# AnalogKeyPad.net
KiCad netlist of a schematic drawn in EAGLE
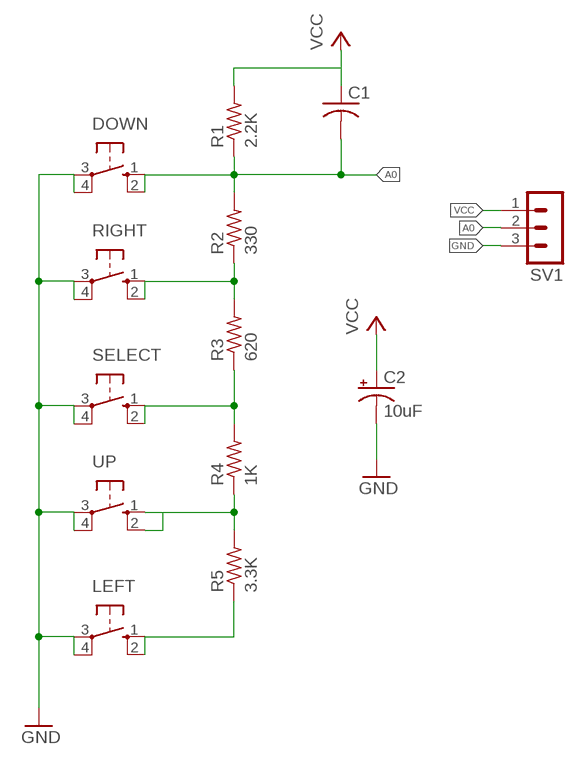
[diagram p0: schematic, sheet 1]

(export (version "E")
  (design (tool "Eeschema 10.0.6"))
  (components
    (comp (ref "C1")
      (value "C-US050-024X044")
      (footprint "eagle-import:C050-024X044")
      (libsource (lib "eagle-import") (part "C-US050-024X044"))
    )
    (comp (ref "C2")
      (value "10uF")
      (footprint "eagle-import:E2,5-6E")
      (libsource (lib "eagle-import") (part "CPOL-USE2,5-6E"))
    )
    (comp (ref "DOWN")
      (value "10-XX")
      (footprint "eagle-import:B3F-10XX")
      (fields (field (name "MPN") "B3F-1000"))
      (libsource (lib "eagle-import") (part "10-XX"))
    )
    (comp (ref "LEFT")
      (value "10-XX")
      (footprint "eagle-import:B3F-10XX")
      (fields (field (name "MPN") "B3F-1000"))
      (libsource (lib "eagle-import") (part "10-XX"))
    )
    (comp (ref "R1")
      (value "2.2K")
      (footprint "eagle-import:0207_7")
      (libsource (lib "eagle-import") (part "R-US_0207/7"))
    )
    (comp (ref "R2")
      (value "330")
      (footprint "eagle-import:0207_7")
      (libsource (lib "eagle-import") (part "R-US_0207/7"))
    )
    (comp (ref "R3")
      (value "620")
      (footprint "eagle-import:0207_7")
      (libsource (lib "eagle-import") (part "R-US_0207/7"))
    )
    (comp (ref "R4")
      (value "1K")
      (footprint "eagle-import:0207_7")
      (libsource (lib "eagle-import") (part "R-US_0207/7"))
    )
    (comp (ref "R5")
      (value "3.3K")
      (footprint "eagle-import:0207_7")
      (libsource (lib "eagle-import") (part "R-US_0207/7"))
    )
    (comp (ref "RIGHT")
      (value "10-XX")
      (footprint "eagle-import:B3F-10XX")
      (fields (field (name "MPN") "B3F-1000"))
      (libsource (lib "eagle-import") (part "10-XX"))
    )
    (comp (ref "SELECT")
      (value "10-XX")
      (footprint "eagle-import:B3F-10XX")
      (fields (field (name "MPN") "B3F-1000"))
      (libsource (lib "eagle-import") (part "10-XX"))
    )
    (comp (ref "SV1")
      (value "MA03-1")
      (footprint "eagle-import:MA03-1")
      (libsource (lib "eagle-import") (part "MA03-1"))
    )
    (comp (ref "UP")
      (value "10-XX")
      (footprint "eagle-import:B3F-10XX")
      (fields (field (name "MPN") "B3F-1000"))
      (libsource (lib "eagle-import") (part "10-XX"))
    )
  )
  (nets
    (net (code "1") (name "A0") (class "Default")
      (node (ref "C1") (pin "2") (pinfunction "2_2") (pintype "passive"))
      (node (ref "DOWN") (pin "1") (pinfunction "S_1") (pintype "passive"))
      (node (ref "DOWN") (pin "2") (pinfunction "S1_2") (pintype "passive"))
      (node (ref "R1") (pin "1") (pinfunction "1_1") (pintype "passive"))
      (node (ref "R2") (pin "2") (pinfunction "2_2") (pintype "passive"))
      (node (ref "SV1") (pin "2") (pinfunction "2_2") (pintype "passive"))
    )
    (net (code "2") (name "GND") (class "Default")
      (node (ref "C2") (pin "-") (pinfunction "-_-") (pintype "passive"))
      (node (ref "DOWN") (pin "3") (pinfunction "P_3") (pintype "passive"))
      (node (ref "DOWN") (pin "4") (pinfunction "P1_4") (pintype "passive"))
      (node (ref "LEFT") (pin "3") (pinfunction "P_3") (pintype "passive"))
      (node (ref "LEFT") (pin "4") (pinfunction "P1_4") (pintype "passive"))
      (node (ref "RIGHT") (pin "3") (pinfunction "P_3") (pintype "passive"))
      (node (ref "RIGHT") (pin "4") (pinfunction "P1_4") (pintype "passive"))
      (node (ref "SELECT") (pin "3") (pinfunction "P_3") (pintype "passive"))
      (node (ref "SELECT") (pin "4") (pinfunction "P1_4") (pintype "passive"))
      (node (ref "SV1") (pin "3") (pinfunction "3_3") (pintype "passive"))
      (node (ref "UP") (pin "3") (pinfunction "P_3") (pintype "passive"))
      (node (ref "UP") (pin "4") (pinfunction "P1_4") (pintype "passive"))
    )
    (net (code "3") (name "Net-(LEFT-S)") (class "Default")
      (node (ref "LEFT") (pin "1") (pinfunction "S_1") (pintype "passive"))
      (node (ref "LEFT") (pin "2") (pinfunction "S1_2") (pintype "passive"))
      (node (ref "R5") (pin "1") (pinfunction "1_1") (pintype "passive"))
    )
    (net (code "4") (name "Net-(RIGHT-S)") (class "Default")
      (node (ref "R2") (pin "1") (pinfunction "1_1") (pintype "passive"))
      (node (ref "R3") (pin "2") (pinfunction "2_2") (pintype "passive"))
      (node (ref "RIGHT") (pin "1") (pinfunction "S_1") (pintype "passive"))
      (node (ref "RIGHT") (pin "2") (pinfunction "S1_2") (pintype "passive"))
    )
    (net (code "5") (name "Net-(SELECT-S)") (class "Default")
      (node (ref "R3") (pin "1") (pinfunction "1_1") (pintype "passive"))
      (node (ref "R4") (pin "2") (pinfunction "2_2") (pintype "passive"))
      (node (ref "SELECT") (pin "1") (pinfunction "S_1") (pintype "passive"))
      (node (ref "SELECT") (pin "2") (pinfunction "S1_2") (pintype "passive"))
    )
    (net (code "6") (name "Net-(UP-S)") (class "Default")
      (node (ref "R4") (pin "1") (pinfunction "1_1") (pintype "passive"))
      (node (ref "R5") (pin "2") (pinfunction "2_2") (pintype "passive"))
      (node (ref "UP") (pin "1") (pinfunction "S_1") (pintype "passive"))
      (node (ref "UP") (pin "2") (pinfunction "S1_2") (pintype "passive"))
    )
    (net (code "7") (name "VCC") (class "Default")
      (node (ref "C1") (pin "1") (pinfunction "1_1") (pintype "passive"))
      (node (ref "C2") (pin "+") (pinfunction "+_+") (pintype "passive"))
      (node (ref "R1") (pin "2") (pinfunction "2_2") (pintype "passive"))
      (node (ref "SV1") (pin "1") (pinfunction "1_1") (pintype "passive"))
    )
  )
)
